# BLDC_V1.net
KiCad netlist of a schematic drawn in Altium Designer
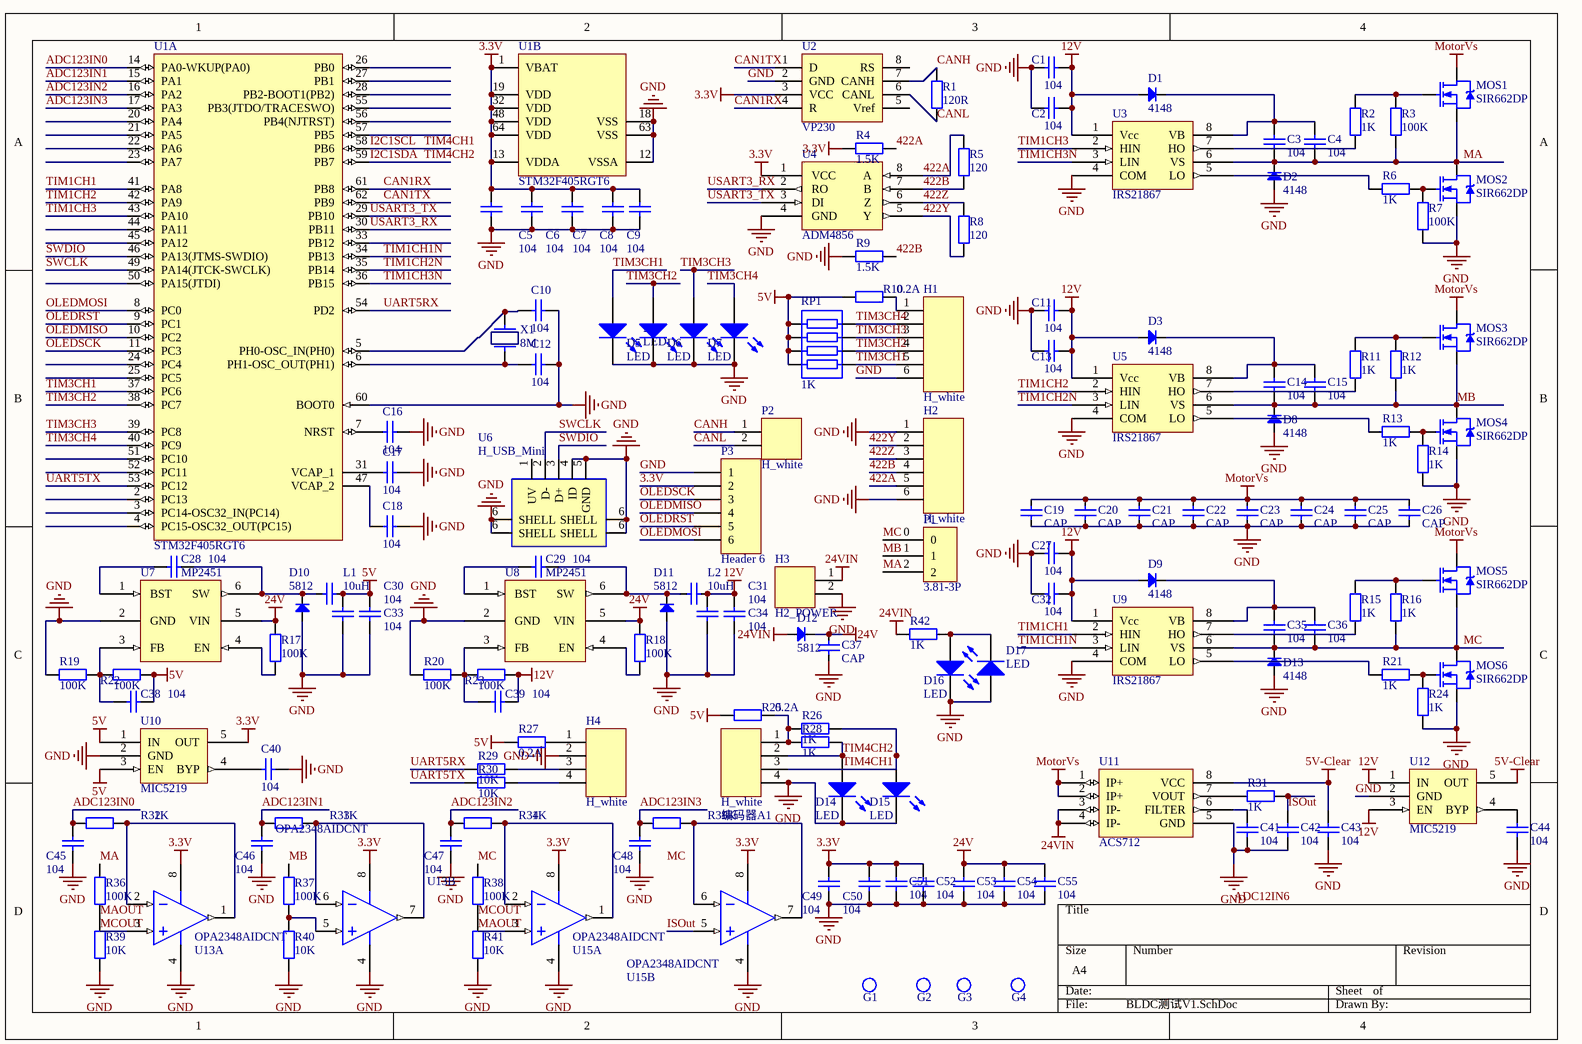
[diagram p0: BLDC测试V1.SchDoc]

(export (version "E")
  (design (tool "Eeschema 10.0.6"))
  (components
    (comp (ref "C1")
      (value "104")
      (footprint "0805C")
      (libsource (lib "lucifer-PCBLIB_V2.0（这是老蒋的）") (part "cap"))
    )
    (comp (ref "C2")
      (value "104")
      (footprint "0805C")
      (libsource (lib "lucifer-PCBLIB_V2.0（这是老蒋的）") (part "cap"))
    )
    (comp (ref "C3")
      (value "104")
      (footprint "0805C")
      (libsource (lib "lucifer-PCBLIB_V2.0（这是老蒋的）") (part "cap"))
    )
    (comp (ref "C4")
      (value "104")
      (footprint "0805C")
      (libsource (lib "lucifer-PCBLIB_V2.0（这是老蒋的）") (part "cap"))
    )
    (comp (ref "C5")
      (value "104")
      (footprint "0805C")
      (libsource (lib "lucifer-PCBLIB_V2.0（这是老蒋的）") (part "cap"))
    )
    (comp (ref "C6")
      (value "104")
      (footprint "0805C")
      (libsource (lib "lucifer-PCBLIB_V2.0（这是老蒋的）") (part "cap"))
    )
    (comp (ref "C7")
      (value "104")
      (footprint "0805C")
      (libsource (lib "lucifer-PCBLIB_V2.0（这是老蒋的）") (part "cap"))
    )
    (comp (ref "C8")
      (value "104")
      (footprint "0805C")
      (libsource (lib "lucifer-PCBLIB_V2.0（这是老蒋的）") (part "cap"))
    )
    (comp (ref "C9")
      (value "104")
      (footprint "0805C")
      (libsource (lib "lucifer-PCBLIB_V2.0（这是老蒋的）") (part "cap"))
    )
    (comp (ref "C10")
      (value "104")
      (footprint "0603C")
      (libsource (lib "lucifer-PCBLIB_V2.0（这是老蒋的）") (part "cap"))
    )
    (comp (ref "C11")
      (value "104")
      (footprint "0805C")
      (libsource (lib "lucifer-PCBLIB_V2.0（这是老蒋的）") (part "cap"))
    )
    (comp (ref "C12")
      (value "104")
      (footprint "0603C")
      (libsource (lib "lucifer-PCBLIB_V2.0（这是老蒋的）") (part "cap"))
    )
    (comp (ref "C13")
      (value "104")
      (footprint "0805C")
      (libsource (lib "lucifer-PCBLIB_V2.0（这是老蒋的）") (part "cap"))
    )
    (comp (ref "C14")
      (value "104")
      (footprint "0805C")
      (libsource (lib "lucifer-PCBLIB_V2.0（这是老蒋的）") (part "cap"))
    )
    (comp (ref "C15")
      (value "104")
      (footprint "0805C")
      (libsource (lib "lucifer-PCBLIB_V2.0（这是老蒋的）") (part "cap"))
    )
    (comp (ref "C16")
      (value "104")
      (footprint "0603C")
      (libsource (lib "lucifer-PCBLIB_V2.0（这是老蒋的）") (part "cap"))
    )
    (comp (ref "C17")
      (value "104")
      (footprint "0805C")
      (libsource (lib "lucifer-PCBLIB_V2.0（这是老蒋的）") (part "cap"))
    )
    (comp (ref "C18")
      (value "104")
      (footprint "0805C")
      (libsource (lib "lucifer-PCBLIB_V2.0（这是老蒋的）") (part "cap"))
    )
    (comp (ref "C19") (value "CAP") (footprint "1210") (libsource (lib "机器人队元件库") (part "CAP")))
    (comp (ref "C20") (value "CAP") (footprint "1210") (libsource (lib "机器人队元件库") (part "CAP")))
    (comp (ref "C21") (value "CAP") (footprint "1210") (libsource (lib "机器人队元件库") (part "CAP")))
    (comp (ref "C22") (value "CAP") (footprint "1210") (libsource (lib "机器人队元件库") (part "CAP")))
    (comp (ref "C23") (value "CAP") (footprint "1210") (libsource (lib "机器人队元件库") (part "CAP")))
    (comp (ref "C24") (value "CAP") (footprint "1210") (libsource (lib "机器人队元件库") (part "CAP")))
    (comp (ref "C25") (value "CAP") (footprint "1210") (libsource (lib "机器人队元件库") (part "CAP")))
    (comp (ref "C26") (value "CAP") (footprint "1210") (libsource (lib "机器人队元件库") (part "CAP")))
    (comp (ref "C27")
      (value "104")
      (footprint "0805C")
      (libsource (lib "lucifer-PCBLIB_V2.0（这是老蒋的）") (part "cap"))
    )
    (comp (ref "C28")
      (value "104")
      (footprint "0603C")
      (libsource (lib "lucifer-PCBLIB_V2.0（这是老蒋的）") (part "cap"))
    )
    (comp (ref "C29")
      (value "104")
      (footprint "0603C")
      (libsource (lib "lucifer-PCBLIB_V2.0（这是老蒋的）") (part "cap"))
    )
    (comp (ref "C30")
      (value "104")
      (footprint "0805C")
      (libsource (lib "lucifer-PCBLIB_V2.0（这是老蒋的）") (part "cap"))
    )
    (comp (ref "C31")
      (value "104")
      (footprint "0805C")
      (libsource (lib "lucifer-PCBLIB_V2.0（这是老蒋的）") (part "cap"))
    )
    (comp (ref "C32")
      (value "104")
      (footprint "0805C")
      (libsource (lib "lucifer-PCBLIB_V2.0（这是老蒋的）") (part "cap"))
    )
    (comp (ref "C33")
      (value "104")
      (footprint "0805C")
      (libsource (lib "lucifer-PCBLIB_V2.0（这是老蒋的）") (part "cap"))
    )
    (comp (ref "C34")
      (value "104")
      (footprint "0805C")
      (libsource (lib "lucifer-PCBLIB_V2.0（这是老蒋的）") (part "cap"))
    )
    (comp (ref "C35")
      (value "104")
      (footprint "0805C")
      (libsource (lib "lucifer-PCBLIB_V2.0（这是老蒋的）") (part "cap"))
    )
    (comp (ref "C36")
      (value "104")
      (footprint "0805C")
      (libsource (lib "lucifer-PCBLIB_V2.0（这是老蒋的）") (part "cap"))
    )
    (comp (ref "C37") (value "CAP") (footprint "1210") (libsource (lib "机器人队元件库") (part "CAP")))
    (comp (ref "C38")
      (value "104")
      (footprint "0603C")
      (libsource (lib "lucifer-PCBLIB_V2.0（这是老蒋的）") (part "cap"))
    )
    (comp (ref "C39")
      (value "104")
      (footprint "0603C")
      (libsource (lib "lucifer-PCBLIB_V2.0（这是老蒋的）") (part "cap"))
    )
    (comp (ref "C40")
      (value "104")
      (footprint "0805C")
      (libsource (lib "lucifer-PCBLIB_V2.0（这是老蒋的）") (part "cap"))
    )
    (comp (ref "C41")
      (value "104")
      (footprint "0603C")
      (libsource (lib "lucifer-PCBLIB_V2.0（这是老蒋的）") (part "cap"))
    )
    (comp (ref "C42")
      (value "104")
      (footprint "0603C")
      (libsource (lib "lucifer-PCBLIB_V2.0（这是老蒋的）") (part "cap"))
    )
    (comp (ref "C43")
      (value "104")
      (footprint "0805C")
      (libsource (lib "lucifer-PCBLIB_V2.0（这是老蒋的）") (part "cap"))
    )
    (comp (ref "C44")
      (value "104")
      (footprint "0603C")
      (libsource (lib "lucifer-PCBLIB_V2.0（这是老蒋的）") (part "cap"))
    )
    (comp (ref "C45")
      (value "104")
      (footprint "0603C")
      (libsource (lib "lucifer-PCBLIB_V2.0（这是老蒋的）") (part "cap"))
    )
    (comp (ref "C46")
      (value "104")
      (footprint "0603C")
      (libsource (lib "lucifer-PCBLIB_V2.0（这是老蒋的）") (part "cap"))
    )
    (comp (ref "C47")
      (value "104")
      (footprint "0603C")
      (libsource (lib "lucifer-PCBLIB_V2.0（这是老蒋的）") (part "cap"))
    )
    (comp (ref "C48")
      (value "104")
      (footprint "0603C")
      (libsource (lib "lucifer-PCBLIB_V2.0（这是老蒋的）") (part "cap"))
    )
    (comp (ref "C49")
      (value "104")
      (footprint "0603C")
      (libsource (lib "lucifer-PCBLIB_V2.0（这是老蒋的）") (part "cap"))
    )
    (comp (ref "C50")
      (value "104")
      (footprint "0603C")
      (libsource (lib "lucifer-PCBLIB_V2.0（这是老蒋的）") (part "cap"))
    )
    (comp (ref "C51")
      (value "104")
      (footprint "0805C")
      (libsource (lib "lucifer-PCBLIB_V2.0（这是老蒋的）") (part "cap"))
    )
    (comp (ref "C52")
      (value "104")
      (footprint "0805C")
      (libsource (lib "lucifer-PCBLIB_V2.0（这是老蒋的）") (part "cap"))
    )
    (comp (ref "C53")
      (value "104")
      (footprint "0805C")
      (libsource (lib "lucifer-PCBLIB_V2.0（这是老蒋的）") (part "cap"))
    )
    (comp (ref "C54")
      (value "104")
      (footprint "0805C")
      (libsource (lib "lucifer-PCBLIB_V2.0（这是老蒋的）") (part "cap"))
    )
    (comp (ref "C55")
      (value "104")
      (footprint "0805C")
      (libsource (lib "lucifer-PCBLIB_V2.0（这是老蒋的）") (part "cap"))
    )
    (comp (ref "D1")
      (value "4148")
      (footprint "1206D")
      (libsource (lib "lucifer-PCBLIB_V2.0（这是老蒋的）") (part "diode 4148"))
    )
    (comp (ref "D2")
      (value "4148")
      (footprint "1206D")
      (libsource (lib "lucifer-PCBLIB_V2.0（这是老蒋的）") (part "diode 4148"))
    )
    (comp (ref "D3")
      (value "4148")
      (footprint "1206D")
      (libsource (lib "lucifer-PCBLIB_V2.0（这是老蒋的）") (part "diode 4148"))
    )
    (comp (ref "D4")
      (value "LED")
      (footprint "0805P")
      (libsource (lib "lucifer-PCBLIB_V2.0（这是老蒋的）") (part "LED"))
    )
    (comp (ref "D5")
      (value "LED")
      (footprint "0805P")
      (libsource (lib "lucifer-PCBLIB_V2.0（这是老蒋的）") (part "LED"))
    )
    (comp (ref "D6")
      (value "LED")
      (footprint "0805P")
      (libsource (lib "lucifer-PCBLIB_V2.0（这是老蒋的）") (part "LED"))
    )
    (comp (ref "D7")
      (value "LED")
      (footprint "0805P")
      (libsource (lib "lucifer-PCBLIB_V2.0（这是老蒋的）") (part "LED"))
    )
    (comp (ref "D8")
      (value "4148")
      (footprint "1206D")
      (libsource (lib "lucifer-PCBLIB_V2.0（这是老蒋的）") (part "diode 4148"))
    )
    (comp (ref "D9")
      (value "4148")
      (footprint "1206D")
      (libsource (lib "lucifer-PCBLIB_V2.0（这是老蒋的）") (part "diode 4148"))
    )
    (comp (ref "D10")
      (value "5812")
      (footprint "1206D")
      (libsource (lib "lucifer-PCBLIB_V2.0（这是老蒋的）") (part "diode 4148"))
    )
    (comp (ref "D11")
      (value "5812")
      (footprint "1206D")
      (libsource (lib "lucifer-PCBLIB_V2.0（这是老蒋的）") (part "diode 4148"))
    )
    (comp (ref "D12")
      (value "5812")
      (footprint "1206D")
      (libsource (lib "lucifer-PCBLIB_V2.0（这是老蒋的）") (part "diode 4148"))
    )
    (comp (ref "D13")
      (value "4148")
      (footprint "1206D")
      (libsource (lib "lucifer-PCBLIB_V2.0（这是老蒋的）") (part "diode 4148"))
    )
    (comp (ref "D14")
      (value "LED")
      (footprint "0805P")
      (libsource (lib "lucifer-PCBLIB_V2.0（这是老蒋的）") (part "LED"))
    )
    (comp (ref "D15")
      (value "LED")
      (footprint "0805P")
      (libsource (lib "lucifer-PCBLIB_V2.0（这是老蒋的）") (part "LED"))
    )
    (comp (ref "D16")
      (value "LED")
      (footprint "0805P")
      (libsource (lib "lucifer-PCBLIB_V2.0（这是老蒋的）") (part "LED"))
    )
    (comp (ref "D17")
      (value "LED")
      (footprint "0805P")
      (libsource (lib "lucifer-PCBLIB_V2.0（这是老蒋的）") (part "LED"))
    )
    (comp (ref "G1")
      (value "M3过孔")
      (footprint "M3过孔")
      (libsource (lib "lucifer-PCBLIB_V2.0（这是老蒋的）") (part "M3过孔"))
    )
    (comp (ref "G2")
      (value "M3过孔")
      (footprint "M3过孔")
      (libsource (lib "lucifer-PCBLIB_V2.0（这是老蒋的）") (part "M3过孔"))
    )
    (comp (ref "G3")
      (value "M3过孔")
      (footprint "M3过孔")
      (libsource (lib "lucifer-PCBLIB_V2.0（这是老蒋的）") (part "M3过孔"))
    )
    (comp (ref "G4")
      (value "M3过孔")
      (footprint "M3过孔")
      (libsource (lib "lucifer-PCBLIB_V2.0（这是老蒋的）") (part "M3过孔"))
    )
    (comp (ref "H1")
      (value "H_white")
      (footprint "H6_white")
      (libsource (lib "机器人队元件库") (part "header6 white"))
    )
    (comp (ref "H2")
      (value "H_white")
      (footprint "H6_white")
      (libsource (lib "机器人队元件库") (part "header6 white"))
    )
    (comp (ref "H3") (value "H2_POWER") (footprint "H2_Power") (libsource (lib "机器人队元件库") (part "H2_POWER")))
    (comp (ref "H4")
      (value "H_white")
      (footprint "H4_white")
      (libsource (lib "机器人队元件库") (part "header4 white"))
    )
    (comp (ref "L1") (value "10uH") (footprint "1210") (libsource (lib "机器人队元件库") (part "CAP")))
    (comp (ref "L2") (value "10uH") (footprint "1210") (libsource (lib "机器人队元件库") (part "CAP")))
    (comp (ref "MOS1")
      (value "SIR662DP")
      (footprint "POWERPACK-8")
      (libsource (lib "Integrated_Library1") (part "SIR662DP"))
    )
    (comp (ref "MOS2")
      (value "SIR662DP")
      (footprint "POWERPACK-8")
      (libsource (lib "Integrated_Library1") (part "SIR662DP"))
    )
    (comp (ref "MOS3")
      (value "SIR662DP")
      (footprint "POWERPACK-8")
      (libsource (lib "Integrated_Library1") (part "SIR662DP"))
    )
    (comp (ref "MOS4")
      (value "SIR662DP")
      (footprint "POWERPACK-8")
      (libsource (lib "Integrated_Library1") (part "SIR662DP"))
    )
    (comp (ref "MOS5")
      (value "SIR662DP")
      (footprint "POWERPACK-8")
      (libsource (lib "Integrated_Library1") (part "SIR662DP"))
    )
    (comp (ref "MOS6")
      (value "SIR662DP")
      (footprint "POWERPACK-8")
      (libsource (lib "Integrated_Library1") (part "SIR662DP"))
    )
    (comp (ref "P1")
      (value "3.81-3P")
      (footprint "校队的端子-3.81-3P")
      (libsource (lib "Integrated_Library1") (part "校队端子-3.81-3P"))
    )
    (comp (ref "P2")
      (value "H_white")
      (footprint "H2_white")
      (libsource (lib "机器人队元件库") (part "header2 white"))
    )
    (comp (ref "P3")
      (value "Header 6")
      (footprint "HDR1X6")
      (description "Header, 6-Pin")
      (fields (field (name "PUBLISHER") "Altium Limited"))
      (libsource (lib "Miscellaneous Connectors") (part "Header 6"))
    )
    (comp (ref "R1")
      (value "120R")
      (footprint "0603")
      (description "small resistor")
      (libsource (lib "") (part "resistor_1"))
    )
    (comp (ref "R2")
      (value "1K")
      (footprint "0603")
      (description "small resistor")
      (libsource (lib "") (part "resistor_2"))
    )
    (comp (ref "R3")
      (value "100K")
      (footprint "0603")
      (description "small resistor")
      (libsource (lib "") (part "resistor_1"))
    )
    (comp (ref "R4")
      (value "1.5K")
      (footprint "0603")
      (description "small resistor")
      (libsource (lib "lucifer-PCBLIB_V2.0（这是老蒋的）") (part "resistor"))
    )
    (comp (ref "R5")
      (value "120")
      (footprint "0603")
      (description "small resistor")
      (libsource (lib "") (part "resistor_2"))
    )
    (comp (ref "R6")
      (value "1K")
      (footprint "0603")
      (description "small resistor")
      (libsource (lib "") (part "resistor_3"))
    )
    (comp (ref "R7")
      (value "100K")
      (footprint "0603")
      (description "small resistor")
      (libsource (lib "") (part "resistor_2"))
    )
    (comp (ref "R8")
      (value "120")
      (footprint "0603")
      (description "small resistor")
      (libsource (lib "") (part "resistor_3"))
    )
    (comp (ref "R9")
      (value "1.5K")
      (footprint "0603")
      (description "small resistor")
      (libsource (lib "lucifer-PCBLIB_V2.0（这是老蒋的）") (part "resistor"))
    )
    (comp (ref "R10")
      (value "0.2A")
      (footprint "0603")
      (description "small resistor")
      (libsource (lib "lucifer-PCBLIB_V2.0（这是老蒋的）") (part "resistor"))
    )
    (comp (ref "R11")
      (value "1K")
      (footprint "0603")
      (description "small resistor")
      (libsource (lib "") (part "resistor_2"))
    )
    (comp (ref "R12")
      (value "1K")
      (footprint "0603")
      (description "small resistor")
      (libsource (lib "") (part "resistor_1"))
    )
    (comp (ref "R13")
      (value "1K")
      (footprint "0603")
      (description "small resistor")
      (libsource (lib "") (part "resistor_3"))
    )
    (comp (ref "R14")
      (value "1K")
      (footprint "0603")
      (description "small resistor")
      (libsource (lib "") (part "resistor_2"))
    )
    (comp (ref "R15")
      (value "1K")
      (footprint "0603")
      (description "small resistor")
      (libsource (lib "") (part "resistor_2"))
    )
    (comp (ref "R16")
      (value "1K")
      (footprint "0603")
      (description "small resistor")
      (libsource (lib "") (part "resistor_1"))
    )
    (comp (ref "R17")
      (value "100K")
      (footprint "0603")
      (description "small resistor")
      (libsource (lib "") (part "resistor_2"))
    )
    (comp (ref "R18")
      (value "100K")
      (footprint "0603")
      (description "small resistor")
      (libsource (lib "") (part "resistor_2"))
    )
    (comp (ref "R19")
      (value "100K")
      (footprint "0603")
      (description "small resistor")
      (libsource (lib "lucifer-PCBLIB_V2.0（这是老蒋的）") (part "resistor"))
    )
    (comp (ref "R20")
      (value "100K")
      (footprint "0603")
      (description "small resistor")
      (libsource (lib "lucifer-PCBLIB_V2.0（这是老蒋的）") (part "resistor"))
    )
    (comp (ref "R21")
      (value "1K")
      (footprint "0603")
      (description "small resistor")
      (libsource (lib "") (part "resistor_3"))
    )
    (comp (ref "R22")
      (value "100K")
      (footprint "0603")
      (description "small resistor")
      (libsource (lib "lucifer-PCBLIB_V2.0（这是老蒋的）") (part "resistor"))
    )
    (comp (ref "R23")
      (value "100K")
      (footprint "0603")
      (description "small resistor")
      (libsource (lib "lucifer-PCBLIB_V2.0（这是老蒋的）") (part "resistor"))
    )
    (comp (ref "R24")
      (value "1K")
      (footprint "0603")
      (description "small resistor")
      (libsource (lib "") (part "resistor_2"))
    )
    (comp (ref "R25")
      (value "0.2A")
      (footprint "0603")
      (description "small resistor")
      (libsource (lib "lucifer-PCBLIB_V2.0（这是老蒋的）") (part "resistor"))
    )
    (comp (ref "R26")
      (value "1K")
      (footprint "0805")
      (description "small resistor")
      (libsource (lib "") (part "resistor_3"))
    )
    (comp (ref "R27")
      (value "0.2A")
      (footprint "0603")
      (description "small resistor")
      (libsource (lib "lucifer-PCBLIB_V2.0（这是老蒋的）") (part "resistor"))
    )
    (comp (ref "R28")
      (value "1K")
      (footprint "0805")
      (description "small resistor")
      (libsource (lib "") (part "resistor_3"))
    )
    (comp (ref "R29")
      (value "10K")
      (footprint "0805")
      (description "small resistor")
      (libsource (lib "lucifer-PCBLIB_V2.0（这是老蒋的）") (part "resistor"))
    )
    (comp (ref "R30")
      (value "10K")
      (footprint "0805")
      (description "small resistor")
      (libsource (lib "lucifer-PCBLIB_V2.0（这是老蒋的）") (part "resistor"))
    )
    (comp (ref "R31")
      (value "1K")
      (footprint "0603")
      (description "small resistor")
      (libsource (lib "") (part "resistor_3"))
    )
    (comp (ref "R32")
      (value "1K")
      (footprint "0603")
      (description "small resistor")
      (libsource (lib "lucifer-PCBLIB_V2.0（这是老蒋的）") (part "resistor"))
    )
    (comp (ref "R33")
      (value "1K")
      (footprint "0603")
      (description "small resistor")
      (libsource (lib "lucifer-PCBLIB_V2.0（这是老蒋的）") (part "resistor"))
    )
    (comp (ref "R34")
      (value "1K")
      (footprint "0603")
      (description "small resistor")
      (libsource (lib "lucifer-PCBLIB_V2.0（这是老蒋的）") (part "resistor"))
    )
    (comp (ref "R35")
      (value "1K")
      (footprint "0603")
      (description "small resistor")
      (libsource (lib "lucifer-PCBLIB_V2.0（这是老蒋的）") (part "resistor"))
    )
    (comp (ref "R36")
      (value "100K")
      (footprint "0603")
      (description "small resistor")
      (libsource (lib "") (part "resistor_1"))
    )
    (comp (ref "R37")
      (value "100K")
      (footprint "0603")
      (description "small resistor")
      (libsource (lib "") (part "resistor_1"))
    )
    (comp (ref "R38")
      (value "100K")
      (footprint "0603")
      (description "small resistor")
      (libsource (lib "") (part "resistor_1"))
    )
    (comp (ref "R39")
      (value "10K")
      (footprint "0603")
      (description "small resistor")
      (libsource (lib "") (part "resistor_1"))
    )
    (comp (ref "R40")
      (value "10K")
      (footprint "0603")
      (description "small resistor")
      (libsource (lib "") (part "resistor_1"))
    )
    (comp (ref "R41")
      (value "10K")
      (footprint "0603")
      (description "small resistor")
      (libsource (lib "") (part "resistor_1"))
    )
    (comp (ref "R42")
      (value "1K")
      (footprint "0805")
      (description "small resistor")
      (libsource (lib "") (part "resistor_3"))
    )
    (comp (ref "RP1")
      (value "1K")
      (footprint "RESPACK 8P4R 0603")
      (libsource (lib "lucifer-PCBLIB_V2.0（这是老蒋的）") (part "RESPACK4 8P4R"))
    )
    (comp (ref "U1")
      (value "STM32F405RGT6")
      (footprint "STM-LQFP64_N")
      (fields (field (name "MANUFACTURER") "STMicroelectronics"))
      (libsource (lib "STMicroelectronics STM32 F4") (part "STM32F405RGT6"))
    )
    (comp (ref "U2") (value "VP230") (footprint "SOIC-8") (libsource (lib "主控-3.1") (part "VP230")))
    (comp (ref "U3")
      (value "IRS21867")
      (footprint "SOIC-NB-8")
      (libsource (lib "Integrated_Library1") (part "IRS21867"))
    )
    (comp (ref "U4")
      (value "ADM4856")
      (footprint "SOIC-NB-8")
      (libsource (lib "Integrated_Library1") (part "ADM4856"))
    )
    (comp (ref "U5")
      (value "IRS21867")
      (footprint "SOIC-NB-8")
      (libsource (lib "Integrated_Library1") (part "IRS21867"))
    )
    (comp (ref "U6")
      (value "H_USB_Mini")
      (footprint "H_USB_Mini_A")
      (description "MiniUSB头母头")
      (libsource (lib "顶板 V1.3") (part "H_USB_Mini"))
    )
    (comp (ref "U7")
      (value "MP2451")
      (footprint "SOT23-6")
      (libsource (lib "Integrated_Library1") (part "MP2451"))
    )
    (comp (ref "U8")
      (value "MP2451")
      (footprint "SOT23-6")
      (libsource (lib "Integrated_Library1") (part "MP2451"))
    )
    (comp (ref "U9")
      (value "IRS21867")
      (footprint "SOIC-NB-8")
      (libsource (lib "Integrated_Library1") (part "IRS21867"))
    )
    (comp (ref "U10")
      (value "MIC5219")
      (footprint "SOT23-5")
      (libsource (lib "Integrated_Library1") (part "MIC5219"))
    )
    (comp (ref "U11")
      (value "ACS712")
      (footprint "SOIC-NB-8")
      (libsource (lib "Integrated_Library1") (part "ACS712"))
    )
    (comp (ref "U12")
      (value "MIC5219")
      (footprint "SOT23-5")
      (libsource (lib "Integrated_Library1") (part "MIC5219"))
    )
    (comp (ref "U13")
      (value "OPA2348AIDCNT")
      (footprint "TI-DCN8_N")
      (fields (field (name "MANUFACTURER") "Texas Instruments"))
      (libsource (lib "TI Amplifiers and Linear Operational Amplifier Precision Amplifier Part One") (part "OPA2348AIDCNT"))
    )
    (comp (ref "U15")
      (value "OPA2348AIDCNT")
      (footprint "TI-DCN8_N")
      (fields (field (name "MANUFACTURER") "Texas Instruments"))
      (libsource (lib "TI Amplifiers and Linear Operational Amplifier Precision Amplifier Part One") (part "OPA2348AIDCNT"))
    )
    (comp (ref "X1")
      (value "8M")
      (footprint "XTAL_DIP")
      (fields (field (name "Comment") "xtal"))
      (libsource (lib "lucifer-PCBLIB_V2.0（这是老蒋的）") (part "xtal"))
    )
    (comp (ref "编码器A1")
      (value "H_white")
      (footprint "H4_white")
      (libsource (lib "") (part "header4 white_1"))
    )
  )
  (nets
    (net (code "1") (name "/422A") (class "Default")
      (node (ref "H2") (pin "5") (pinfunction "5_5") (pintype "passive"))
      (node (ref "R4") (pin "1") (pinfunction "1_1") (pintype "passive"))
      (node (ref "R5") (pin "2") (pinfunction "2_2") (pintype "passive"))
      (node (ref "U4") (pin "8") (pinfunction "A_8") (pintype "input"))
    )
    (net (code "2") (name "/422B") (class "Default")
      (node (ref "H2") (pin "4") (pinfunction "4_4") (pintype "passive"))
      (node (ref "R5") (pin "1") (pinfunction "1_1") (pintype "passive"))
      (node (ref "R9") (pin "1") (pinfunction "1_1") (pintype "passive"))
      (node (ref "U4") (pin "7") (pinfunction "B_7") (pintype "input"))
    )
    (net (code "3") (name "/422Y") (class "Default")
      (node (ref "H2") (pin "2") (pinfunction "2_2") (pintype "passive"))
      (node (ref "R8") (pin "1") (pinfunction "1_1") (pintype "passive"))
      (node (ref "U4") (pin "5") (pinfunction "Y_5") (pintype "output"))
    )
    (net (code "4") (name "/422Z") (class "Default")
      (node (ref "H2") (pin "3") (pinfunction "3_3") (pintype "passive"))
      (node (ref "R8") (pin "2") (pinfunction "2_2") (pintype "passive"))
      (node (ref "U4") (pin "6") (pinfunction "Z_6") (pintype "output"))
    )
    (net (code "6") (name "/ADC123IN0") (class "Default")
      (node (ref "C45") (pin "1") (pinfunction "1_1") (pintype "passive"))
      (node (ref "R32") (pin "2") (pinfunction "2_2") (pintype "passive"))
      (node (ref "U1") (pin "14") (pinfunction "PA0-WKUP(PA0)_14") (pintype "bidirectional"))
    )
    (net (code "7") (name "/ADC123IN1") (class "Default")
      (node (ref "C46") (pin "1") (pinfunction "1_1") (pintype "passive"))
      (node (ref "R33") (pin "2") (pinfunction "2_2") (pintype "passive"))
      (node (ref "U1") (pin "15") (pinfunction "PA1_15") (pintype "bidirectional"))
    )
    (net (code "8") (name "/ADC123IN2") (class "Default")
      (node (ref "C47") (pin "1") (pinfunction "1_1") (pintype "passive"))
      (node (ref "R34") (pin "2") (pinfunction "2_2") (pintype "passive"))
      (node (ref "U1") (pin "16") (pinfunction "PA2_16") (pintype "bidirectional"))
    )
    (net (code "9") (name "/ADC123IN3") (class "Default")
      (node (ref "C48") (pin "1") (pinfunction "1_1") (pintype "passive"))
      (node (ref "R35") (pin "2") (pinfunction "2_2") (pintype "passive"))
      (node (ref "U1") (pin "17") (pinfunction "PA3_17") (pintype "bidirectional"))
    )
    (net (code "10") (name "/CAN1RX") (class "Default")
      (node (ref "U1") (pin "61") (pinfunction "PB8_61") (pintype "bidirectional"))
      (node (ref "U2") (pin "4") (pinfunction "R_4") (pintype "power_in"))
    )
    (net (code "11") (name "/CAN1TX") (class "Default")
      (node (ref "U1") (pin "62") (pinfunction "PB9_62") (pintype "bidirectional"))
      (node (ref "U2") (pin "1") (pinfunction "D_1") (pintype "power_in"))
    )
    (net (code "12") (name "/CANH") (class "Default")
      (node (ref "P2") (pin "1") (pinfunction "1_1") (pintype "passive"))
      (node (ref "R1") (pin "1") (pinfunction "1_1") (pintype "passive"))
      (node (ref "U2") (pin "7") (pinfunction "CANH_7") (pintype "power_in"))
    )
    (net (code "13") (name "/CANL") (class "Default")
      (node (ref "P2") (pin "2") (pinfunction "2_2") (pintype "passive"))
      (node (ref "R1") (pin "2") (pinfunction "2_2") (pintype "passive"))
      (node (ref "U2") (pin "6") (pinfunction "CANL_6") (pintype "power_in"))
    )
    (net (code "14") (name "/I2C1SCL") (class "Default")
      (node (ref "D15") (pin "1") (pinfunction "A_1") (pintype "passive"))
      (node (ref "R26") (pin "2") (pinfunction "2_2") (pintype "passive"))
      (node (ref "U1") (pin "58") (pinfunction "PB6_58") (pintype "bidirectional"))
      (node (ref "编码器A1") (pin "3") (pinfunction "3_3") (pintype "passive"))
    )
    (net (code "15") (name "/I2C1SDA") (class "Default")
      (node (ref "D14") (pin "1") (pinfunction "A_1") (pintype "passive"))
      (node (ref "R28") (pin "2") (pinfunction "2_2") (pintype "passive"))
      (node (ref "U1") (pin "59") (pinfunction "PB7_59") (pintype "bidirectional"))
      (node (ref "编码器A1") (pin "2") (pinfunction "2_2") (pintype "passive"))
    )
    (net (code "16") (name "/ISOut") (class "Default")
      (node (ref "C42") (pin "1") (pinfunction "1_1") (pintype "passive"))
      (node (ref "R31") (pin "2") (pinfunction "2_2") (pintype "passive"))
      (node (ref "U15") (pin "5") (pinfunction "IN_B+_5") (pintype "input"))
    )
    (net (code "17") (name "/MA") (class "Default")
      (node (ref "C3") (pin "1") (pinfunction "1_1") (pintype "passive"))
      (node (ref "C4") (pin "1") (pinfunction "1_1") (pintype "passive"))
      (node (ref "D2") (pin "2") (pinfunction "K_2") (pintype "passive"))
      (node (ref "MOS1") (pin "S") (pinfunction "S_S") (pintype "passive"))
      (node (ref "MOS2") (pin "D") (pinfunction "D_D") (pintype "passive"))
      (node (ref "P1") (pin "2") (pinfunction "2_2") (pintype "power_in"))
      (node (ref "R3") (pin "2") (pinfunction "2_2") (pintype "passive"))
      (node (ref "R36") (pin "1") (pinfunction "1_1") (pintype "passive"))
      (node (ref "U3") (pin "6") (pinfunction "VS_6") (pintype "power_in"))
    )
    (net (code "18") (name "/MAOUT") (class "Default")
      (node (ref "R36") (pin "2") (pinfunction "2_2") (pintype "passive"))
      (node (ref "R39") (pin "1") (pinfunction "1_1") (pintype "passive"))
      (node (ref "U15") (pin "3") (pinfunction "IN_A+_3") (pintype "input"))
    )
    (net (code "19") (name "/MB") (class "Default")
      (node (ref "C14") (pin "1") (pinfunction "1_1") (pintype "passive"))
      (node (ref "C15") (pin "1") (pinfunction "1_1") (pintype "passive"))
      (node (ref "D8") (pin "2") (pinfunction "K_2") (pintype "passive"))
      (node (ref "MOS3") (pin "S") (pinfunction "S_S") (pintype "passive"))
      (node (ref "MOS4") (pin "D") (pinfunction "D_D") (pintype "passive"))
      (node (ref "P1") (pin "1") (pinfunction "1_1") (pintype "power_in"))
      (node (ref "R12") (pin "2") (pinfunction "2_2") (pintype "passive"))
      (node (ref "R37") (pin "1") (pinfunction "1_1") (pintype "passive"))
      (node (ref "U5") (pin "6") (pinfunction "VS_6") (pintype "power_in"))
    )
    (net (code "20") (name "/MC") (class "Default")
      (node (ref "C35") (pin "1") (pinfunction "1_1") (pintype "passive"))
      (node (ref "C36") (pin "1") (pinfunction "1_1") (pintype "passive"))
      (node (ref "D13") (pin "2") (pinfunction "K_2") (pintype "passive"))
      (node (ref "MOS5") (pin "S") (pinfunction "S_S") (pintype "passive"))
      (node (ref "MOS6") (pin "D") (pinfunction "D_D") (pintype "passive"))
      (node (ref "P1") (pin "0") (pinfunction "0_0") (pintype "power_in"))
      (node (ref "R16") (pin "2") (pinfunction "2_2") (pintype "passive"))
      (node (ref "R38") (pin "1") (pinfunction "1_1") (pintype "passive"))
      (node (ref "U9") (pin "6") (pinfunction "VS_6") (pintype "power_in"))
    )
    (net (code "21") (name "/MCOUT") (class "Default")
      (node (ref "R38") (pin "2") (pinfunction "2_2") (pintype "passive"))
      (node (ref "R41") (pin "1") (pinfunction "1_1") (pintype "passive"))
      (node (ref "U13") (pin "3") (pinfunction "IN_A+_3") (pintype "input"))
    )
    (net (code "22") (name "/OLEDMISO") (class "Default")
      (node (ref "P3") (pin "4") (pinfunction "4_4") (pintype "passive"))
      (node (ref "U1") (pin "10") (pinfunction "PC2_10") (pintype "bidirectional"))
    )
    (net (code "23") (name "/OLEDMOSI") (class "Default")
      (node (ref "P3") (pin "6") (pinfunction "6_6") (pintype "passive"))
      (node (ref "U1") (pin "8") (pinfunction "PC0_8") (pintype "bidirectional"))
    )
    (net (code "24") (name "/OLEDRST") (class "Default")
      (node (ref "P3") (pin "5") (pinfunction "5_5") (pintype "passive"))
      (node (ref "U1") (pin "9") (pinfunction "PC1_9") (pintype "bidirectional"))
    )
    (net (code "25") (name "/OLEDSCK") (class "Default")
      (node (ref "P3") (pin "3") (pinfunction "3_3") (pintype "passive"))
      (node (ref "U1") (pin "11") (pinfunction "PC3_11") (pintype "bidirectional"))
    )
    (net (code "26") (name "/SWCLK") (class "Default")
      (node (ref "U1") (pin "49") (pinfunction "PA14(JTCK-SWCLK)_49") (pintype "bidirectional"))
      (node (ref "U6") (pin "2") (pinfunction "D-_2") (pintype "passive"))
    )
    (net (code "27") (name "/SWDIO") (class "Default")
      (node (ref "U1") (pin "46") (pinfunction "PA13(JTMS-SWDIO)_46") (pintype "bidirectional"))
      (node (ref "U6") (pin "3") (pinfunction "D+_3") (pintype "passive"))
    )
    (net (code "28") (name "/TIM1CH1") (class "Default")
      (node (ref "U1") (pin "41") (pinfunction "PA8_41") (pintype "bidirectional"))
      (node (ref "U9") (pin "2") (pinfunction "HIN_2") (pintype "input"))
    )
    (net (code "29") (name "/TIM1CH1N") (class "Default")
      (node (ref "U1") (pin "34") (pinfunction "PB13_34") (pintype "bidirectional"))
      (node (ref "U9") (pin "3") (pinfunction "LIN_3") (pintype "input"))
    )
    (net (code "30") (name "/TIM1CH2") (class "Default")
      (node (ref "U1") (pin "42") (pinfunction "PA9_42") (pintype "bidirectional"))
      (node (ref "U5") (pin "2") (pinfunction "HIN_2") (pintype "input"))
    )
    (net (code "31") (name "/TIM1CH2N") (class "Default")
      (node (ref "U1") (pin "35") (pinfunction "PB14_35") (pintype "bidirectional"))
      (node (ref "U5") (pin "3") (pinfunction "LIN_3") (pintype "input"))
    )
    (net (code "32") (name "/TIM1CH3") (class "Default")
      (node (ref "U1") (pin "43") (pinfunction "PA10_43") (pintype "bidirectional"))
      (node (ref "U3") (pin "2") (pinfunction "HIN_2") (pintype "input"))
    )
    (net (code "33") (name "/TIM1CH3N") (class "Default")
      (node (ref "U1") (pin "36") (pinfunction "PB15_36") (pintype "bidirectional"))
      (node (ref "U3") (pin "3") (pinfunction "LIN_3") (pintype "input"))
    )
    (net (code "34") (name "/TIM3CH1") (class "Default")
      (node (ref "D4") (pin "1") (pinfunction "A_1") (pintype "passive"))
      (node (ref "H1") (pin "5") (pinfunction "5_5") (pintype "passive"))
      (node (ref "RP1") (pin "8") (pintype "passive"))
      (node (ref "U1") (pin "37") (pinfunction "PC6_37") (pintype "bidirectional"))
    )
    (net (code "35") (name "/TIM3CH2") (class "Default")
      (node (ref "D5") (pin "1") (pinfunction "A_1") (pintype "passive"))
      (node (ref "H1") (pin "4") (pinfunction "4_4") (pintype "passive"))
      (node (ref "RP1") (pin "6") (pintype "passive"))
      (node (ref "U1") (pin "38") (pinfunction "PC7_38") (pintype "bidirectional"))
    )
    (net (code "36") (name "/TIM3CH3") (class "Default")
      (node (ref "D6") (pin "1") (pinfunction "A_1") (pintype "passive"))
      (node (ref "H1") (pin "3") (pinfunction "3_3") (pintype "passive"))
      (node (ref "RP1") (pin "4") (pintype "passive"))
      (node (ref "U1") (pin "39") (pinfunction "PC8_39") (pintype "bidirectional"))
    )
    (net (code "37") (name "/TIM3CH4") (class "Default")
      (node (ref "D7") (pin "1") (pinfunction "A_1") (pintype "passive"))
      (node (ref "H1") (pin "2") (pinfunction "2_2") (pintype "passive"))
      (node (ref "RP1") (pin "2") (pintype "passive"))
      (node (ref "U1") (pin "40") (pinfunction "PC9_40") (pintype "bidirectional"))
    )
    (net (code "38") (name "/UART5RX") (class "Default")
      (node (ref "R29") (pin "2") (pinfunction "2_2") (pintype "passive"))
      (node (ref "U1") (pin "54") (pinfunction "PD2_54") (pintype "bidirectional"))
    )
    (net (code "39") (name "/UART5TX") (class "Default")
      (node (ref "R30") (pin "2") (pinfunction "2_2") (pintype "passive"))
      (node (ref "U1") (pin "53") (pinfunction "PC12_53") (pintype "bidirectional"))
    )
    (net (code "40") (name "/USART3_RX") (class "Default")
      (node (ref "U1") (pin "30") (pinfunction "PB11_30") (pintype "bidirectional"))
      (node (ref "U4") (pin "2") (pinfunction "RO_2") (pintype "output"))
    )
    (net (code "41") (name "/USART3_TX") (class "Default")
      (node (ref "U1") (pin "29") (pinfunction "PB10_29") (pintype "bidirectional"))
      (node (ref "U4") (pin "3") (pinfunction "DI_3") (pintype "input"))
    )
    (net (code "42") (name "3.3V") (class "Default")
      (node (ref "C49") (pin "1") (pinfunction "1_1") (pintype "passive"))
      (node (ref "C5") (pin "2") (pinfunction "2_2") (pintype "passive"))
      (node (ref "C50") (pin "1") (pinfunction "1_1") (pintype "passive"))
      (node (ref "C51") (pin "2") (pinfunction "2_2") (pintype "passive"))
      (node (ref "C52") (pin "2") (pinfunction "2_2") (pintype "passive"))
      (node (ref "C6") (pin "1") (pinfunction "1_1") (pintype "passive"))
      (node (ref "C7") (pin "1") (pinfunction "1_1") (pintype "passive"))
      (node (ref "C8") (pin "1") (pinfunction "1_1") (pintype "passive"))
      (node (ref "C9") (pin "2") (pinfunction "2_2") (pintype "passive"))
      (node (ref "P3") (pin "2") (pinfunction "2_2") (pintype "passive"))
      (node (ref "R4") (pin "2") (pinfunction "2_2") (pintype "passive"))
      (node (ref "U1") (pin "1") (pinfunction "VBAT_1") (pintype "power_in"))
      (node (ref "U1") (pin "13") (pinfunction "VDDA_13") (pintype "power_in"))
      (node (ref "U1") (pin "19") (pinfunction "VDD_19") (pintype "power_in"))
      (node (ref "U1") (pin "32") (pinfunction "VDD_32") (pintype "power_in"))
      (node (ref "U1") (pin "48") (pinfunction "VDD_48") (pintype "power_in"))
      (node (ref "U1") (pin "64") (pinfunction "VDD_64") (pintype "power_in"))
      (node (ref "U10") (pin "5") (pinfunction "OUT_5") (pintype "power_in"))
      (node (ref "U13") (pin "8") (pinfunction "V+_8") (pintype "power_in"))
      (node (ref "U15") (pin "8") (pinfunction "V+_8") (pintype "power_in"))
      (node (ref "U2") (pin "3") (pinfunction "VCC_3") (pintype "power_in"))
      (node (ref "U4") (pin "1") (pinfunction "VCC_1") (pintype "power_in"))
    )
    (net (code "43") (name "5V") (class "Default")
      (node (ref "C30") (pin "2") (pinfunction "2_2") (pintype "passive"))
      (node (ref "C33") (pin "2") (pinfunction "2_2") (pintype "passive"))
      (node (ref "C38") (pin "2") (pinfunction "2_2") (pintype "passive"))
      (node (ref "L1") (pin "2") (pintype "passive"))
      (node (ref "R10") (pin "2") (pinfunction "2_2") (pintype "passive"))
      (node (ref "R22") (pin "1") (pinfunction "1_1") (pintype "passive"))
      (node (ref "R25") (pin "2") (pinfunction "2_2") (pintype "passive"))
      (node (ref "R27") (pin "2") (pinfunction "2_2") (pintype "passive"))
      (node (ref "RP1") (pin "1") (pintype "passive"))
      (node (ref "RP1") (pin "3") (pintype "passive"))
      (node (ref "RP1") (pin "5") (pintype "passive"))
      (node (ref "RP1") (pin "7") (pintype "passive"))
      (node (ref "U10") (pin "1") (pinfunction "IN_1") (pintype "power_in"))
      (node (ref "U10") (pin "3") (pinfunction "EN_3") (pintype "input"))
    )
    (net (code "44") (name "5V-Clear") (class "Default")
      (node (ref "C43") (pin "2") (pinfunction "2_2") (pintype "passive"))
      (node (ref "U11") (pin "8") (pinfunction "VCC_8") (pintype "power_in"))
      (node (ref "U12") (pin "5") (pinfunction "OUT_5") (pintype "power_in"))
    )
    (net (code "45") (name "12V") (class "Default")
      (node (ref "C1") (pin "1") (pinfunction "1_1") (pintype "passive"))
      (node (ref "C11") (pin "1") (pinfunction "1_1") (pintype "passive"))
      (node (ref "C13") (pin "1") (pinfunction "1_1") (pintype "passive"))
      (node (ref "C2") (pin "1") (pinfunction "1_1") (pintype "passive"))
      (node (ref "C27") (pin "1") (pinfunction "1_1") (pintype "passive"))
      (node (ref "C31") (pin "2") (pinfunction "2_2") (pintype "passive"))
      (node (ref "C32") (pin "1") (pinfunction "1_1") (pintype "passive"))
      (node (ref "C34") (pin "2") (pinfunction "2_2") (pintype "passive"))
      (node (ref "C39") (pin "2") (pinfunction "2_2") (pintype "passive"))
      (node (ref "D1") (pin "1") (pinfunction "A_1") (pintype "passive"))
      (node (ref "D3") (pin "1") (pinfunction "A_1") (pintype "passive"))
      (node (ref "D9") (pin "1") (pinfunction "A_1") (pintype "passive"))
      (node (ref "L2") (pin "2") (pintype "passive"))
      (node (ref "R23") (pin "1") (pinfunction "1_1") (pintype "passive"))
      (node (ref "U12") (pin "1") (pinfunction "IN_1") (pintype "power_in"))
      (node (ref "U12") (pin "3") (pinfunction "EN_3") (pintype "input"))
      (node (ref "U3") (pin "1") (pinfunction "Vcc_1") (pintype "power_in"))
      (node (ref "U5") (pin "1") (pinfunction "Vcc_1") (pintype "power_in"))
      (node (ref "U9") (pin "1") (pinfunction "Vcc_1") (pintype "power_in"))
    )
    (net (code "46") (name "24V") (class "Default")
      (node (ref "C37") (pin "1") (pintype "passive"))
      (node (ref "C53") (pin "2") (pinfunction "2_2") (pintype "passive"))
      (node (ref "C54") (pin "2") (pinfunction "2_2") (pintype "passive"))
      (node (ref "C55") (pin "2") (pinfunction "2_2") (pintype "passive"))
      (node (ref "D12") (pin "2") (pinfunction "K_2") (pintype "passive"))
      (node (ref "R17") (pin "2") (pinfunction "2_2") (pintype "passive"))
      (node (ref "R18") (pin "2") (pinfunction "2_2") (pintype "passive"))
      (node (ref "U7") (pin "5") (pinfunction "VIN_5") (pintype "power_in"))
      (node (ref "U8") (pin "5") (pinfunction "VIN_5") (pintype "power_in"))
    )
    (net (code "47") (name "24VIN") (class "Default")
      (node (ref "D12") (pin "1") (pinfunction "A_1") (pintype "passive"))
      (node (ref "H3") (pin "1") (pinfunction "1_1") (pintype "passive"))
      (node (ref "R42") (pin "1") (pinfunction "1_1") (pintype "passive"))
      (node (ref "U11") (pin "3") (pinfunction "IP-_3") (pintype "bidirectional"))
      (node (ref "U11") (pin "4") (pinfunction "IP-_4") (pintype "bidirectional"))
    )
    (net (code "48") (name "GND") (class "Default")
      (node (ref "C1") (pin "2") (pinfunction "2_2") (pintype "passive"))
      (node (ref "C10") (pin "2") (pinfunction "2_2") (pintype "passive"))
      (node (ref "C11") (pin "2") (pinfunction "2_2") (pintype "passive"))
      (node (ref "C12") (pin "2") (pinfunction "2_2") (pintype "passive"))
      (node (ref "C13") (pin "2") (pinfunction "2_2") (pintype "passive"))
      (node (ref "C16") (pin "2") (pinfunction "2_2") (pintype "passive"))
      (node (ref "C17") (pin "2") (pinfunction "2_2") (pintype "passive"))
      (node (ref "C18") (pin "2") (pinfunction "2_2") (pintype "passive"))
      (node (ref "C19") (pin "2") (pintype "passive"))
      (node (ref "C2") (pin "2") (pinfunction "2_2") (pintype "passive"))
      (node (ref "C20") (pin "2") (pintype "passive"))
      (node (ref "C21") (pin "2") (pintype "passive"))
      (node (ref "C22") (pin "2") (pintype "passive"))
      (node (ref "C23") (pin "2") (pintype "passive"))
      (node (ref "C24") (pin "2") (pintype "passive"))
      (node (ref "C25") (pin "2") (pintype "passive"))
      (node (ref "C26") (pin "2") (pintype "passive"))
      (node (ref "C27") (pin "2") (pinfunction "2_2") (pintype "passive"))
      (node (ref "C30") (pin "1") (pinfunction "1_1") (pintype "passive"))
      (node (ref "C31") (pin "1") (pinfunction "1_1") (pintype "passive"))
      (node (ref "C32") (pin "2") (pinfunction "2_2") (pintype "passive"))
      (node (ref "C33") (pin "1") (pinfunction "1_1") (pintype "passive"))
      (node (ref "C34") (pin "1") (pinfunction "1_1") (pintype "passive"))
      (node (ref "C37") (pin "2") (pintype "passive"))
      (node (ref "C40") (pin "1") (pinfunction "1_1") (pintype "passive"))
      (node (ref "C41") (pin "2") (pinfunction "2_2") (pintype "passive"))
      (node (ref "C42") (pin "2") (pinfunction "2_2") (pintype "passive"))
      (node (ref "C43") (pin "1") (pinfunction "1_1") (pintype "passive"))
      (node (ref "C44") (pin "1") (pinfunction "1_1") (pintype "passive"))
      (node (ref "C45") (pin "2") (pinfunction "2_2") (pintype "passive"))
      (node (ref "C46") (pin "2") (pinfunction "2_2") (pintype "passive"))
      (node (ref "C47") (pin "2") (pinfunction "2_2") (pintype "passive"))
      (node (ref "C48") (pin "2") (pinfunction "2_2") (pintype "passive"))
      (node (ref "C49") (pin "2") (pinfunction "2_2") (pintype "passive"))
      (node (ref "C5") (pin "1") (pinfunction "1_1") (pintype "passive"))
      (node (ref "C50") (pin "2") (pinfunction "2_2") (pintype "passive"))
      (node (ref "C51") (pin "1") (pinfunction "1_1") (pintype "passive"))
      (node (ref "C52") (pin "1") (pinfunction "1_1") (pintype "passive"))
      (node (ref "C53") (pin "1") (pinfunction "1_1") (pintype "passive"))
      (node (ref "C54") (pin "1") (pinfunction "1_1") (pintype "passive"))
      (node (ref "C55") (pin "1") (pinfunction "1_1") (pintype "passive"))
      (node (ref "C6") (pin "2") (pinfunction "2_2") (pintype "passive"))
      (node (ref "C7") (pin "2") (pinfunction "2_2") (pintype "passive"))
      (node (ref "C8") (pin "2") (pinfunction "2_2") (pintype "passive"))
      (node (ref "C9") (pin "1") (pinfunction "1_1") (pintype "passive"))
      (node (ref "D10") (pin "1") (pinfunction "A_1") (pintype "passive"))
      (node (ref "D11") (pin "1") (pinfunction "A_1") (pintype "passive"))
      (node (ref "D13") (pin "1") (pinfunction "A_1") (pintype "passive"))
      (node (ref "D14") (pin "2") (pinfunction "K_2") (pintype "passive"))
      (node (ref "D15") (pin "2") (pinfunction "K_2") (pintype "passive"))
      (node (ref "D16") (pin "2") (pinfunction "K_2") (pintype "passive"))
      (node (ref "D17") (pin "1") (pinfunction "A_1") (pintype "passive"))
      (node (ref "D2") (pin "1") (pinfunction "A_1") (pintype "passive"))
      (node (ref "D4") (pin "2") (pinfunction "K_2") (pintype "passive"))
      (node (ref "D5") (pin "2") (pinfunction "K_2") (pintype "passive"))
      (node (ref "D6") (pin "2") (pinfunction "K_2") (pintype "passive"))
      (node (ref "D7") (pin "2") (pinfunction "K_2") (pintype "passive"))
      (node (ref "D8") (pin "1") (pinfunction "A_1") (pintype "passive"))
      (node (ref "H1") (pin "6") (pinfunction "6_6") (pintype "passive"))
      (node (ref "H2") (pin "1") (pinfunction "1_1") (pintype "passive"))
      (node (ref "H2") (pin "6") (pinfunction "6_6") (pintype "passive"))
      (node (ref "H3") (pin "2") (pinfunction "2_2") (pintype "passive"))
      (node (ref "H4") (pin "2") (pinfunction "2_2") (pintype "passive"))
      (node (ref "MOS2") (pin "S") (pinfunction "S_S") (pintype "passive"))
      (node (ref "MOS4") (pin "S") (pinfunction "S_S") (pintype "passive"))
      (node (ref "MOS6") (pin "S") (pinfunction "S_S") (pintype "passive"))
      (node (ref "P3") (pin "1") (pinfunction "1_1") (pintype "passive"))
      (node (ref "R14") (pin "1") (pinfunction "1_1") (pintype "passive"))
      (node (ref "R19") (pin "2") (pinfunction "2_2") (pintype "passive"))
      (node (ref "R20") (pin "2") (pinfunction "2_2") (pintype "passive"))
      (node (ref "R24") (pin "1") (pinfunction "1_1") (pintype "passive"))
      (node (ref "R39") (pin "2") (pinfunction "2_2") (pintype "passive"))
      (node (ref "R40") (pin "2") (pinfunction "2_2") (pintype "passive"))
      (node (ref "R41") (pin "2") (pinfunction "2_2") (pintype "passive"))
      (node (ref "R7") (pin "1") (pinfunction "1_1") (pintype "passive"))
      (node (ref "R9") (pin "2") (pinfunction "2_2") (pintype "passive"))
      (node (ref "U1") (pin "12") (pinfunction "VSSA_12") (pintype "power_in"))
      (node (ref "U1") (pin "18") (pinfunction "VSS_18") (pintype "power_in"))
      (node (ref "U1") (pin "60") (pinfunction "BOOT0_60") (pintype "input"))
      (node (ref "U1") (pin "63") (pinfunction "VSS_63") (pintype "power_in"))
      (node (ref "U10") (pin "2") (pinfunction "GND_2") (pintype "power_in"))
      (node (ref "U11") (pin "5") (pinfunction "GND_5") (pintype "power_in"))
      (node (ref "U12") (pin "2") (pinfunction "GND_2") (pintype "power_in"))
      (node (ref "U13") (pin "4") (pinfunction "V-_4") (pintype "power_in"))
      (node (ref "U15") (pin "4") (pinfunction "V-_4") (pintype "power_in"))
      (node (ref "U2") (pin "2") (pinfunction "GND_2") (pintype "power_in"))
      (node (ref "U3") (pin "4") (pinfunction "COM_4") (pintype "power_in"))
      (node (ref "U4") (pin "4") (pinfunction "GND_4") (pintype "power_in"))
      (node (ref "U5") (pin "4") (pinfunction "COM_4") (pintype "power_in"))
      (node (ref "U6") (pin "4") (pinfunction "ID_4") (pintype "passive"))
      (node (ref "U6") (pin "5") (pinfunction "GND_5") (pintype "passive"))
      (node (ref "U6") (pin "6") (pinfunction "SHELL_6") (pintype "passive"))
      (node (ref "U7") (pin "2") (pinfunction "GND_2") (pintype "power_in"))
      (node (ref "U8") (pin "2") (pinfunction "GND_2") (pintype "power_in"))
      (node (ref "U9") (pin "4") (pinfunction "COM_4") (pintype "power_in"))
      (node (ref "编码器A1") (pin "4") (pinfunction "4_4") (pintype "passive"))
    )
    (net (code "49") (name "MotorVs") (class "Default")
      (node (ref "C19") (pin "1") (pintype "passive"))
      (node (ref "C20") (pin "1") (pintype "passive"))
      (node (ref "C21") (pin "1") (pintype "passive"))
      (node (ref "C22") (pin "1") (pintype "passive"))
      (node (ref "C23") (pin "1") (pintype "passive"))
      (node (ref "C24") (pin "1") (pintype "passive"))
      (node (ref "C25") (pin "1") (pintype "passive"))
      (node (ref "C26") (pin "1") (pintype "passive"))
      (node (ref "MOS1") (pin "D") (pinfunction "D_D") (pintype "passive"))
      (node (ref "MOS3") (pin "D") (pinfunction "D_D") (pintype "passive"))
      (node (ref "MOS5") (pin "D") (pinfunction "D_D") (pintype "passive"))
      (node (ref "U11") (pin "1") (pinfunction "IP+_1") (pintype "bidirectional"))
      (node (ref "U11") (pin "2") (pinfunction "IP+_2") (pintype "bidirectional"))
    )
    (net (code "50") (name "Net-(D1-K)") (class "Default")
      (node (ref "C3") (pin "2") (pinfunction "2_2") (pintype "passive"))
      (node (ref "C4") (pin "2") (pinfunction "2_2") (pintype "passive"))
      (node (ref "D1") (pin "2") (pinfunction "K_2") (pintype "passive"))
      (node (ref "U3") (pin "8") (pinfunction "VB_8") (pintype "power_in"))
    )
    (net (code "51") (name "Net-(D3-K)") (class "Default")
      (node (ref "C14") (pin "2") (pinfunction "2_2") (pintype "passive"))
      (node (ref "C15") (pin "2") (pinfunction "2_2") (pintype "passive"))
      (node (ref "D3") (pin "2") (pinfunction "K_2") (pintype "passive"))
      (node (ref "U5") (pin "8") (pinfunction "VB_8") (pintype "power_in"))
    )
    (net (code "52") (name "Net-(D9-K)") (class "Default")
      (node (ref "C35") (pin "2") (pinfunction "2_2") (pintype "passive"))
      (node (ref "C36") (pin "2") (pinfunction "2_2") (pintype "passive"))
      (node (ref "D9") (pin "2") (pinfunction "K_2") (pintype "passive"))
      (node (ref "U9") (pin "8") (pinfunction "VB_8") (pintype "power_in"))
    )
    (net (code "53") (name "Net-(D10-K)") (class "Default")
      (node (ref "C28") (pin "2") (pinfunction "2_2") (pintype "passive"))
      (node (ref "D10") (pin "2") (pinfunction "K_2") (pintype "passive"))
      (node (ref "L1") (pin "1") (pintype "passive"))
      (node (ref "U7") (pin "6") (pinfunction "SW_6") (pintype "output"))
    )
    (net (code "54") (name "Net-(D11-K)") (class "Default")
      (node (ref "C29") (pin "2") (pinfunction "2_2") (pintype "passive"))
      (node (ref "D11") (pin "2") (pinfunction "K_2") (pintype "passive"))
      (node (ref "L2") (pin "1") (pintype "passive"))
      (node (ref "U8") (pin "6") (pinfunction "SW_6") (pintype "output"))
    )
    (net (code "55") (name "Net-(D16-A)") (class "Default")
      (node (ref "D16") (pin "1") (pinfunction "A_1") (pintype "passive"))
      (node (ref "D17") (pin "2") (pinfunction "K_2") (pintype "passive"))
      (node (ref "R42") (pin "2") (pinfunction "2_2") (pintype "passive"))
    )
    (net (code "56") (name "Net-(H1-Pad1)") (class "Default")
      (node (ref "H1") (pin "1") (pinfunction "1_1") (pintype "passive"))
      (node (ref "R10") (pin "1") (pinfunction "1_1") (pintype "passive"))
    )
    (net (code "57") (name "Net-(H4-Pad1)") (class "Default")
      (node (ref "H4") (pin "1") (pinfunction "1_1") (pintype "passive"))
      (node (ref "R27") (pin "1") (pinfunction "1_1") (pintype "passive"))
    )
    (net (code "58") (name "Net-(H4-Pad3)") (class "Default")
      (node (ref "H4") (pin "3") (pinfunction "3_3") (pintype "passive"))
      (node (ref "R29") (pin "1") (pinfunction "1_1") (pintype "passive"))
    )
    (net (code "59") (name "Net-(H4-Pad4)") (class "Default")
      (node (ref "H4") (pin "4") (pinfunction "4_4") (pintype "passive"))
      (node (ref "R30") (pin "1") (pinfunction "1_1") (pintype "passive"))
    )
    (net (code "60") (name "Net-(MOS1-PadG)") (class "Default")
      (node (ref "MOS1") (pin "G") (pinfunction "G_G") (pintype "passive"))
      (node (ref "R2") (pin "2") (pinfunction "2_2") (pintype "passive"))
      (node (ref "R3") (pin "1") (pinfunction "1_1") (pintype "passive"))
    )
    (net (code "61") (name "Net-(MOS2-PadG)") (class "Default")
      (node (ref "MOS2") (pin "G") (pinfunction "G_G") (pintype "passive"))
      (node (ref "R6") (pin "2") (pinfunction "2_2") (pintype "passive"))
      (node (ref "R7") (pin "2") (pinfunction "2_2") (pintype "passive"))
    )
    (net (code "62") (name "Net-(MOS3-PadG)") (class "Default")
      (node (ref "MOS3") (pin "G") (pinfunction "G_G") (pintype "passive"))
      (node (ref "R11") (pin "2") (pinfunction "2_2") (pintype "passive"))
      (node (ref "R12") (pin "1") (pinfunction "1_1") (pintype "passive"))
    )
    (net (code "63") (name "Net-(MOS4-PadG)") (class "Default")
      (node (ref "MOS4") (pin "G") (pinfunction "G_G") (pintype "passive"))
      (node (ref "R13") (pin "2") (pinfunction "2_2") (pintype "passive"))
      (node (ref "R14") (pin "2") (pinfunction "2_2") (pintype "passive"))
    )
    (net (code "64") (name "Net-(MOS5-PadG)") (class "Default")
      (node (ref "MOS5") (pin "G") (pinfunction "G_G") (pintype "passive"))
      (node (ref "R15") (pin "2") (pinfunction "2_2") (pintype "passive"))
      (node (ref "R16") (pin "1") (pinfunction "1_1") (pintype "passive"))
    )
    (net (code "65") (name "Net-(MOS6-PadG)") (class "Default")
      (node (ref "MOS6") (pin "G") (pinfunction "G_G") (pintype "passive"))
      (node (ref "R21") (pin "2") (pinfunction "2_2") (pintype "passive"))
      (node (ref "R24") (pin "2") (pinfunction "2_2") (pintype "passive"))
    )
    (net (code "66") (name "Net-(R25-Pad1)") (class "Default")
      (node (ref "R25") (pin "1") (pinfunction "1_1") (pintype "passive"))
      (node (ref "R26") (pin "1") (pinfunction "1_1") (pintype "passive"))
      (node (ref "R28") (pin "1") (pinfunction "1_1") (pintype "passive"))
      (node (ref "编码器A1") (pin "1") (pinfunction "1_1") (pintype "passive"))
    )
    (net (code "67") (name "Net-(U1A-NRST)") (class "Default")
      (node (ref "C16") (pin "1") (pinfunction "1_1") (pintype "passive"))
      (node (ref "U1") (pin "7") (pinfunction "NRST_7") (pintype "bidirectional"))
    )
    (net (code "68") (name "Net-(U1A-PH0-OSC_IN(PH0))") (class "Default")
      (node (ref "C10") (pin "1") (pinfunction "1_1") (pintype "passive"))
      (node (ref "U1") (pin "5") (pinfunction "PH0-OSC_IN(PH0)_5") (pintype "bidirectional"))
      (node (ref "X1") (pin "2") (pinfunction "2_2") (pintype "passive"))
    )
    (net (code "69") (name "Net-(U1A-PH1-OSC_OUT(PH1))") (class "Default")
      (node (ref "C12") (pin "1") (pinfunction "1_1") (pintype "passive"))
      (node (ref "U1") (pin "6") (pinfunction "PH1-OSC_OUT(PH1)_6") (pintype "bidirectional"))
      (node (ref "X1") (pin "1") (pinfunction "1_1") (pintype "passive"))
    )
    (net (code "70") (name "Net-(U1A-VCAP_1)") (class "Default")
      (node (ref "C17") (pin "1") (pinfunction "1_1") (pintype "passive"))
      (node (ref "U1") (pin "31") (pinfunction "VCAP_1_31") (pintype "power_in"))
    )
    (net (code "71") (name "Net-(U1A-VCAP_2)") (class "Default")
      (node (ref "C18") (pin "1") (pinfunction "1_1") (pintype "passive"))
      (node (ref "U1") (pin "47") (pinfunction "VCAP_2_47") (pintype "power_in"))
    )
    (net (code "72") (name "Net-(U3-HO)") (class "Default")
      (node (ref "R2") (pin "1") (pinfunction "1_1") (pintype "passive"))
      (node (ref "U3") (pin "7") (pinfunction "HO_7") (pintype "output"))
    )
    (net (code "73") (name "Net-(U3-LO)") (class "Default")
      (node (ref "R6") (pin "1") (pinfunction "1_1") (pintype "passive"))
      (node (ref "U3") (pin "5") (pinfunction "LO_5") (pintype "output"))
    )
    (net (code "74") (name "Net-(U5-HO)") (class "Default")
      (node (ref "R11") (pin "1") (pinfunction "1_1") (pintype "passive"))
      (node (ref "U5") (pin "7") (pinfunction "HO_7") (pintype "output"))
    )
    (net (code "75") (name "Net-(U5-LO)") (class "Default")
      (node (ref "R13") (pin "1") (pinfunction "1_1") (pintype "passive"))
      (node (ref "U5") (pin "5") (pinfunction "LO_5") (pintype "output"))
    )
    (net (code "76") (name "Net-(U7-BST)") (class "Default")
      (node (ref "C28") (pin "1") (pinfunction "1_1") (pintype "passive"))
      (node (ref "U7") (pin "1") (pinfunction "BST_1") (pintype "input"))
    )
    (net (code "77") (name "Net-(U7-EN)") (class "Default")
      (node (ref "R17") (pin "1") (pinfunction "1_1") (pintype "passive"))
      (node (ref "U7") (pin "4") (pinfunction "EN_4") (pintype "input"))
    )
    (net (code "78") (name "Net-(U7-FB)") (class "Default")
      (node (ref "C38") (pin "1") (pinfunction "1_1") (pintype "passive"))
      (node (ref "R19") (pin "1") (pinfunction "1_1") (pintype "passive"))
      (node (ref "R22") (pin "2") (pinfunction "2_2") (pintype "passive"))
      (node (ref "U7") (pin "3") (pinfunction "FB_3") (pintype "input"))
    )
    (net (code "79") (name "Net-(U8-BST)") (class "Default")
      (node (ref "C29") (pin "1") (pinfunction "1_1") (pintype "passive"))
      (node (ref "U8") (pin "1") (pinfunction "BST_1") (pintype "input"))
    )
    (net (code "80") (name "Net-(U8-EN)") (class "Default")
      (node (ref "R18") (pin "1") (pinfunction "1_1") (pintype "passive"))
      (node (ref "U8") (pin "4") (pinfunction "EN_4") (pintype "input"))
    )
    (net (code "81") (name "Net-(U8-FB)") (class "Default")
      (node (ref "C39") (pin "1") (pinfunction "1_1") (pintype "passive"))
      (node (ref "R20") (pin "1") (pinfunction "1_1") (pintype "passive"))
      (node (ref "R23") (pin "2") (pinfunction "2_2") (pintype "passive"))
      (node (ref "U8") (pin "3") (pinfunction "FB_3") (pintype "input"))
    )
    (net (code "82") (name "Net-(U9-HO)") (class "Default")
      (node (ref "R15") (pin "1") (pinfunction "1_1") (pintype "passive"))
      (node (ref "U9") (pin "7") (pinfunction "HO_7") (pintype "output"))
    )
    (net (code "83") (name "Net-(U9-LO)") (class "Default")
      (node (ref "R21") (pin "1") (pinfunction "1_1") (pintype "passive"))
      (node (ref "U9") (pin "5") (pinfunction "LO_5") (pintype "output"))
    )
    (net (code "84") (name "Net-(U10-BYP)") (class "Default")
      (node (ref "C40") (pin "2") (pinfunction "2_2") (pintype "passive"))
      (node (ref "U10") (pin "4") (pinfunction "BYP_4") (pintype "output"))
    )
    (net (code "85") (name "Net-(U11-FILTER)") (class "Default")
      (node (ref "C41") (pin "1") (pinfunction "1_1") (pintype "passive"))
      (node (ref "U11") (pin "6") (pinfunction "FILTER_6") (pintype "output"))
    )
    (net (code "86") (name "Net-(U11-VOUT)") (class "Default")
      (node (ref "R31") (pin "1") (pinfunction "1_1") (pintype "passive"))
      (node (ref "U11") (pin "7") (pinfunction "VOUT_7") (pintype "output"))
    )
    (net (code "87") (name "Net-(U12-BYP)") (class "Default")
      (node (ref "C44") (pin "2") (pinfunction "2_2") (pintype "passive"))
      (node (ref "U12") (pin "4") (pinfunction "BYP_4") (pintype "output"))
    )
    (net (code "88") (name "Net-(U13A-IN_A-)") (class "Default")
      (node (ref "R32") (pin "1") (pinfunction "1_1") (pintype "passive"))
      (node (ref "U13") (pin "1") (pinfunction "OUT_A_1") (pintype "output"))
      (node (ref "U13") (pin "2") (pinfunction "IN_A-_2") (pintype "input"))
    )
    (net (code "89") (name "Net-(U13B-IN_B+)") (class "Default")
      (node (ref "R37") (pin "2") (pinfunction "2_2") (pintype "passive"))
      (node (ref "R40") (pin "1") (pinfunction "1_1") (pintype "passive"))
      (node (ref "U13") (pin "5") (pinfunction "IN_B+_5") (pintype "input"))
    )
    (net (code "90") (name "Net-(U13B-IN_B-)") (class "Default")
      (node (ref "R33") (pin "1") (pinfunction "1_1") (pintype "passive"))
      (node (ref "U13") (pin "6") (pinfunction "IN_B-_6") (pintype "input"))
      (node (ref "U13") (pin "7") (pinfunction "OUT_B_7") (pintype "output"))
    )
    (net (code "91") (name "Net-(U15A-IN_A-)") (class "Default")
      (node (ref "R34") (pin "1") (pinfunction "1_1") (pintype "passive"))
      (node (ref "U15") (pin "1") (pinfunction "OUT_A_1") (pintype "output"))
      (node (ref "U15") (pin "2") (pinfunction "IN_A-_2") (pintype "input"))
    )
    (net (code "92") (name "Net-(U15B-IN_B-)") (class "Default")
      (node (ref "R35") (pin "1") (pinfunction "1_1") (pintype "passive"))
      (node (ref "U15") (pin "6") (pinfunction "IN_B-_6") (pintype "input"))
      (node (ref "U15") (pin "7") (pinfunction "OUT_B_7") (pintype "output"))
    )
    (net (code "93") (name "unconnected-(U1A-PA4-Pad20)") (class "Default")
      (node (ref "U1") (pin "20") (pinfunction "PA4_20") (pintype "bidirectional"))
    )
    (net (code "94") (name "unconnected-(U1A-PA5-Pad21)") (class "Default")
      (node (ref "U1") (pin "21") (pinfunction "PA5_21") (pintype "bidirectional"))
    )
    (net (code "95") (name "unconnected-(U1A-PA6-Pad22)") (class "Default")
      (node (ref "U1") (pin "22") (pinfunction "PA6_22") (pintype "bidirectional"))
    )
    (net (code "96") (name "unconnected-(U1A-PA7-Pad23)") (class "Default")
      (node (ref "U1") (pin "23") (pinfunction "PA7_23") (pintype "bidirectional"))
    )
    (net (code "97") (name "unconnected-(U1A-PA11-Pad44)") (class "Default")
      (node (ref "U1") (pin "44") (pinfunction "PA11_44") (pintype "bidirectional"))
    )
    (net (code "98") (name "unconnected-(U1A-PA12-Pad45)") (class "Default")
      (node (ref "U1") (pin "45") (pinfunction "PA12_45") (pintype "bidirectional"))
    )
    (net (code "99") (name "unconnected-(U1A-PA15(JTDI)-Pad50)") (class "Default")
      (node (ref "U1") (pin "50") (pinfunction "PA15(JTDI)_50") (pintype "bidirectional"))
    )
    (net (code "100") (name "unconnected-(U1A-PB0-Pad26)") (class "Default")
      (node (ref "U1") (pin "26") (pinfunction "PB0_26") (pintype "bidirectional"))
    )
    (net (code "101") (name "unconnected-(U1A-PB1-Pad27)") (class "Default")
      (node (ref "U1") (pin "27") (pinfunction "PB1_27") (pintype "bidirectional"))
    )
    (net (code "102") (name "unconnected-(U1A-PB2-BOOT1(PB2)-Pad28)") (class "Default")
      (node (ref "U1") (pin "28") (pinfunction "PB2-BOOT1(PB2)_28") (pintype "bidirectional"))
    )
    (net (code "103") (name "unconnected-(U1A-PB3(JTDO{slash}TRACESWO)-Pad55)") (class "Default")
      (node (ref "U1") (pin "55") (pinfunction "PB3(JTDO/TRACESWO)_55") (pintype "bidirectional"))
    )
    (net (code "104") (name "unconnected-(U1A-PB4(NJTRST)-Pad56)") (class "Default")
      (node (ref "U1") (pin "56") (pinfunction "PB4(NJTRST)_56") (pintype "bidirectional"))
    )
    (net (code "105") (name "unconnected-(U1A-PB5-Pad57)") (class "Default")
      (node (ref "U1") (pin "57") (pinfunction "PB5_57") (pintype "bidirectional"))
    )
    (net (code "106") (name "unconnected-(U1A-PB12-Pad33)") (class "Default")
      (node (ref "U1") (pin "33") (pinfunction "PB12_33") (pintype "bidirectional"))
    )
    (net (code "107") (name "unconnected-(U1A-PC4-Pad24)") (class "Default")
      (node (ref "U1") (pin "24") (pinfunction "PC4_24") (pintype "bidirectional"))
    )
    (net (code "108") (name "unconnected-(U1A-PC5-Pad25)") (class "Default")
      (node (ref "U1") (pin "25") (pinfunction "PC5_25") (pintype "bidirectional"))
    )
    (net (code "109") (name "unconnected-(U1A-PC10-Pad51)") (class "Default")
      (node (ref "U1") (pin "51") (pinfunction "PC10_51") (pintype "bidirectional"))
    )
    (net (code "110") (name "unconnected-(U1A-PC11-Pad52)") (class "Default")
      (node (ref "U1") (pin "52") (pinfunction "PC11_52") (pintype "bidirectional"))
    )
    (net (code "111") (name "unconnected-(U1A-PC13-Pad2)") (class "Default")
      (node (ref "U1") (pin "2") (pinfunction "PC13_2") (pintype "bidirectional"))
    )
    (net (code "112") (name "unconnected-(U1A-PC14-OSC32_IN(PC14)-Pad3)") (class "Default")
      (node (ref "U1") (pin "3") (pinfunction "PC14-OSC32_IN(PC14)_3") (pintype "bidirectional"))
    )
    (net (code "113") (name "unconnected-(U1A-PC15-OSC32_OUT(PC15)-Pad4)") (class "Default")
      (node (ref "U1") (pin "4") (pinfunction "PC15-OSC32_OUT(PC15)_4") (pintype "bidirectional"))
    )
    (net (code "114") (name "unconnected-(U2-RS-Pad8)") (class "Default")
      (node (ref "U2") (pin "8") (pinfunction "RS_8") (pintype "power_in"))
    )
    (net (code "115") (name "unconnected-(U2-Vref-Pad5)") (class "Default")
      (node (ref "U2") (pin "5") (pinfunction "Vref_5") (pintype "power_in"))
    )
    (net (code "116") (name "unconnected-(U6-UV-Pad1)") (class "Default")
      (node (ref "U6") (pin "1") (pinfunction "UV_1") (pintype "passive"))
    )
  )
)
